# board.net
KiCad netlist of a schematic drawn in EAGLE
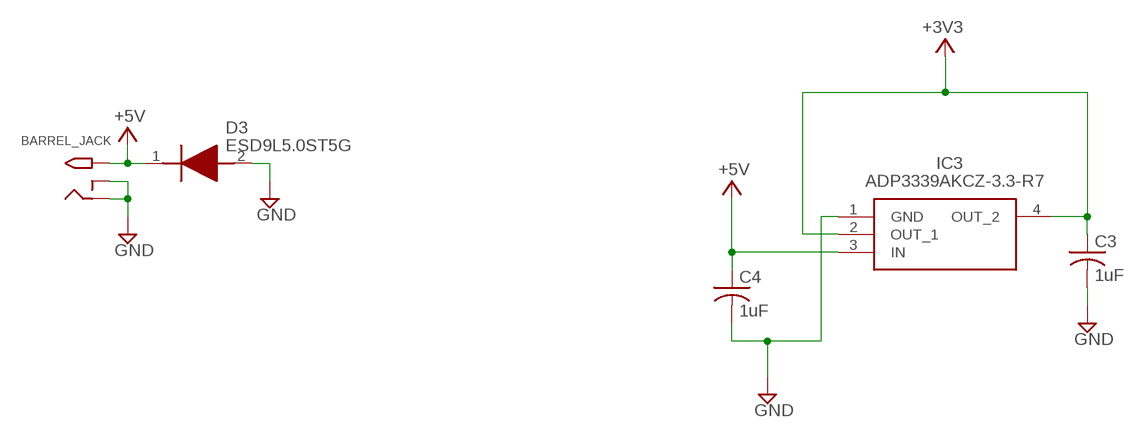
[diagram p0: schematic, sheet 1]
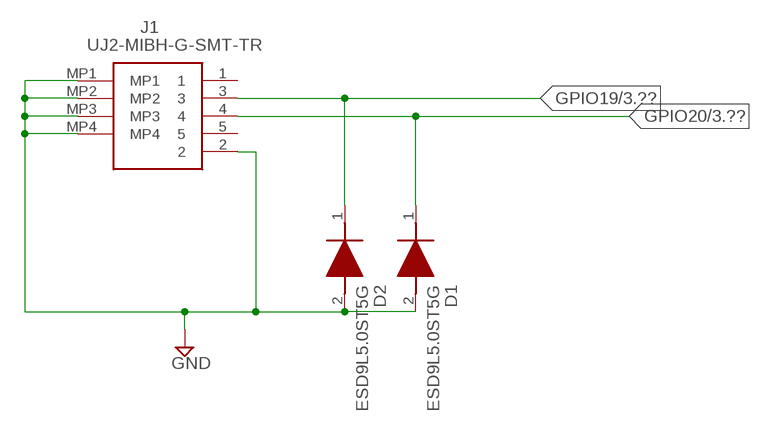
[diagram p1: schematic, sheet 2]
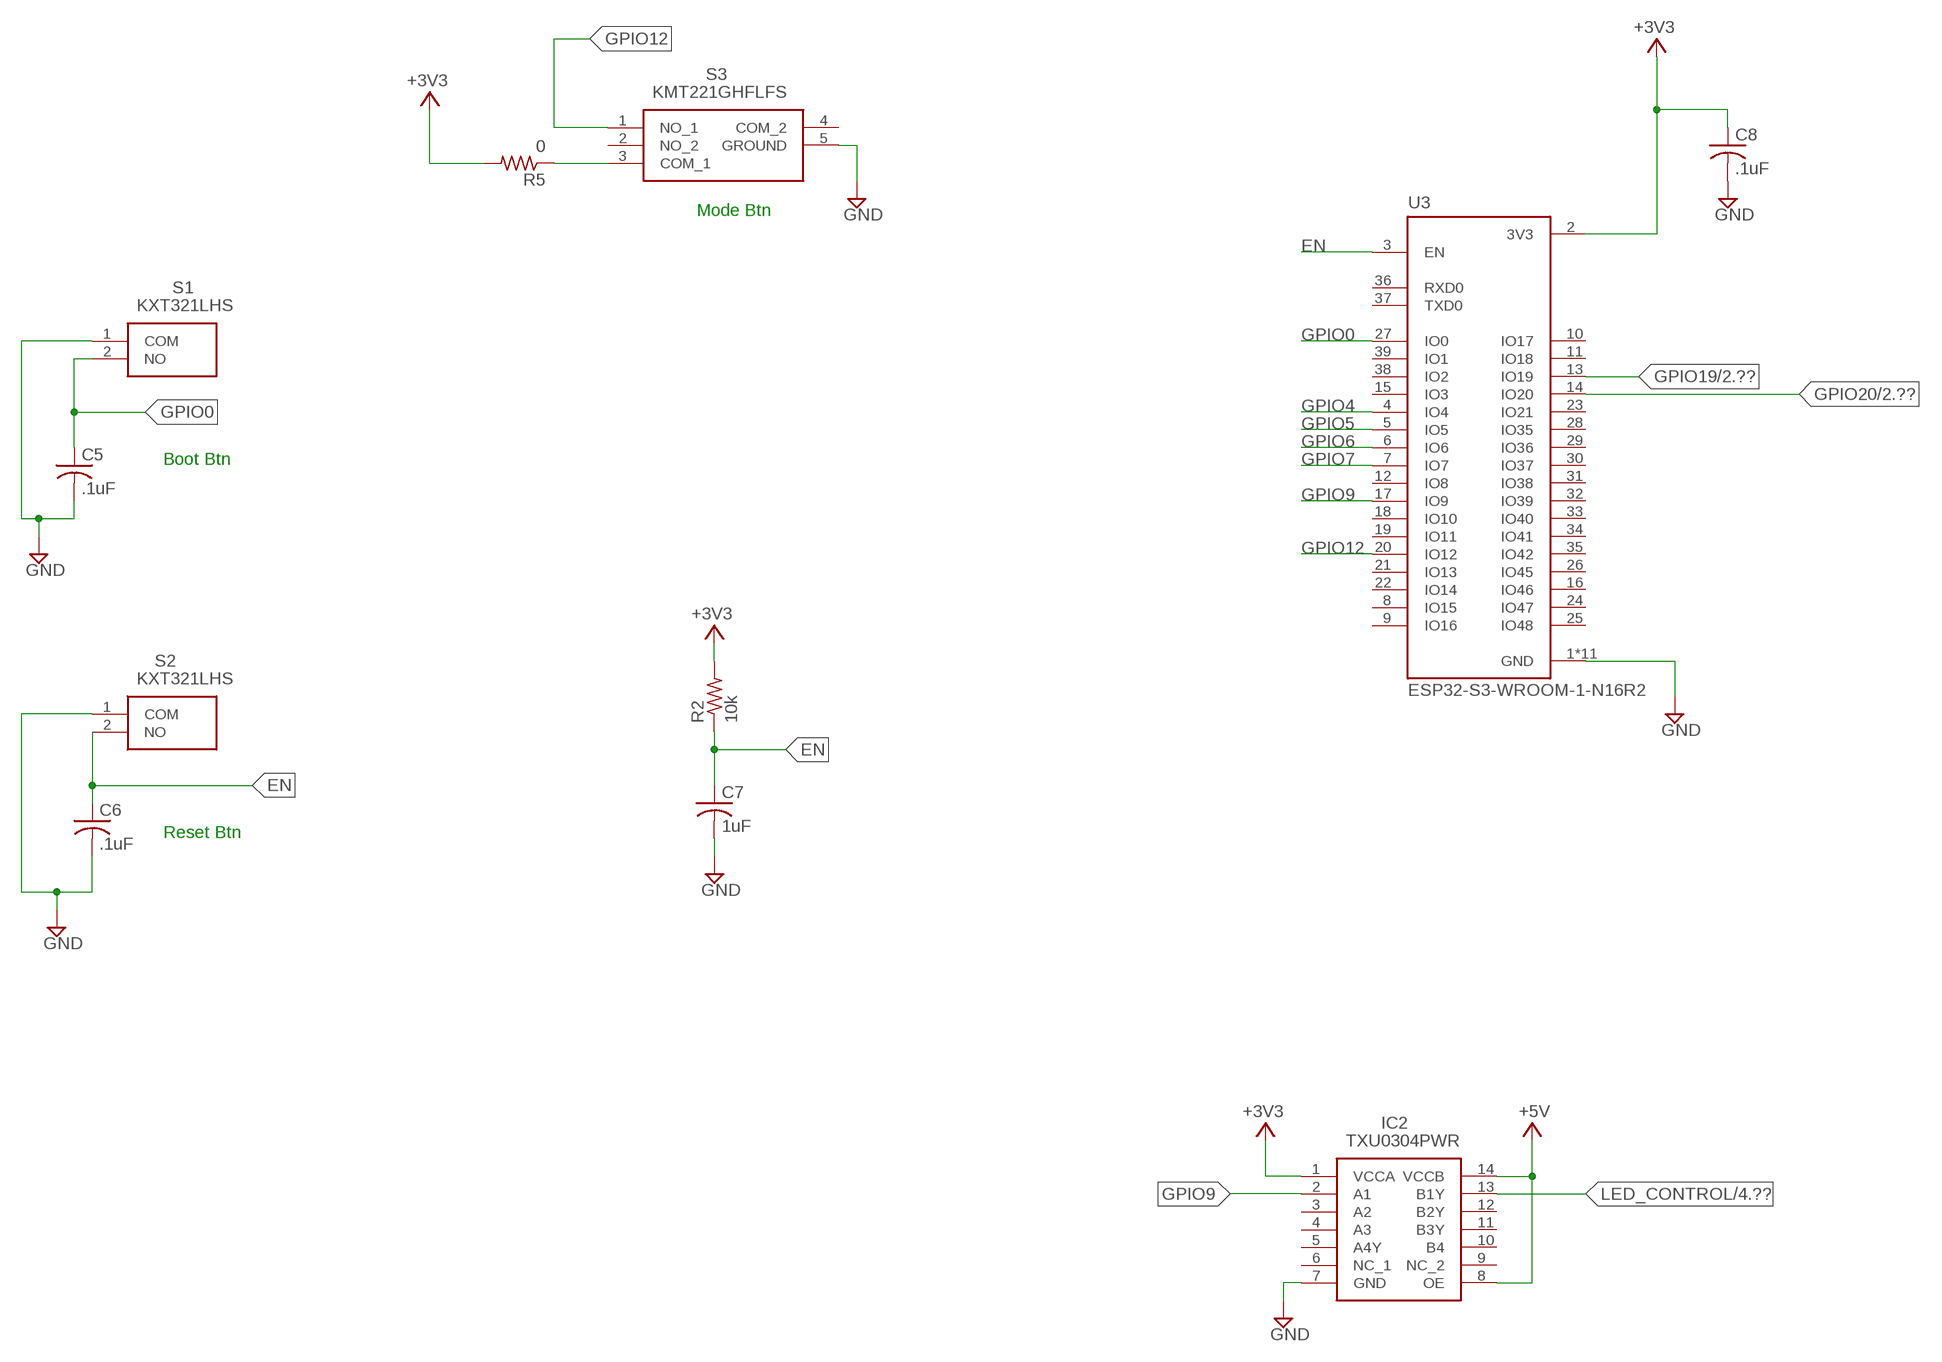
[diagram p2: schematic, sheet 3]
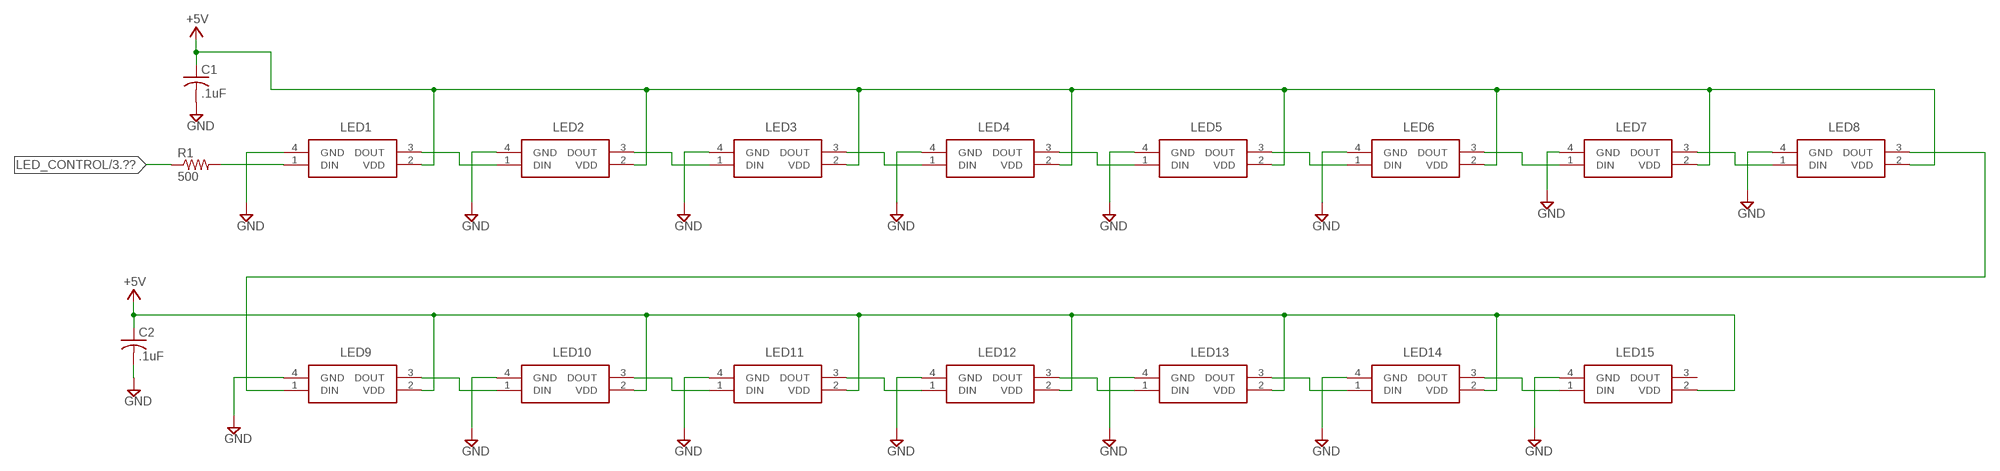
[diagram p3: schematic, sheet 4]
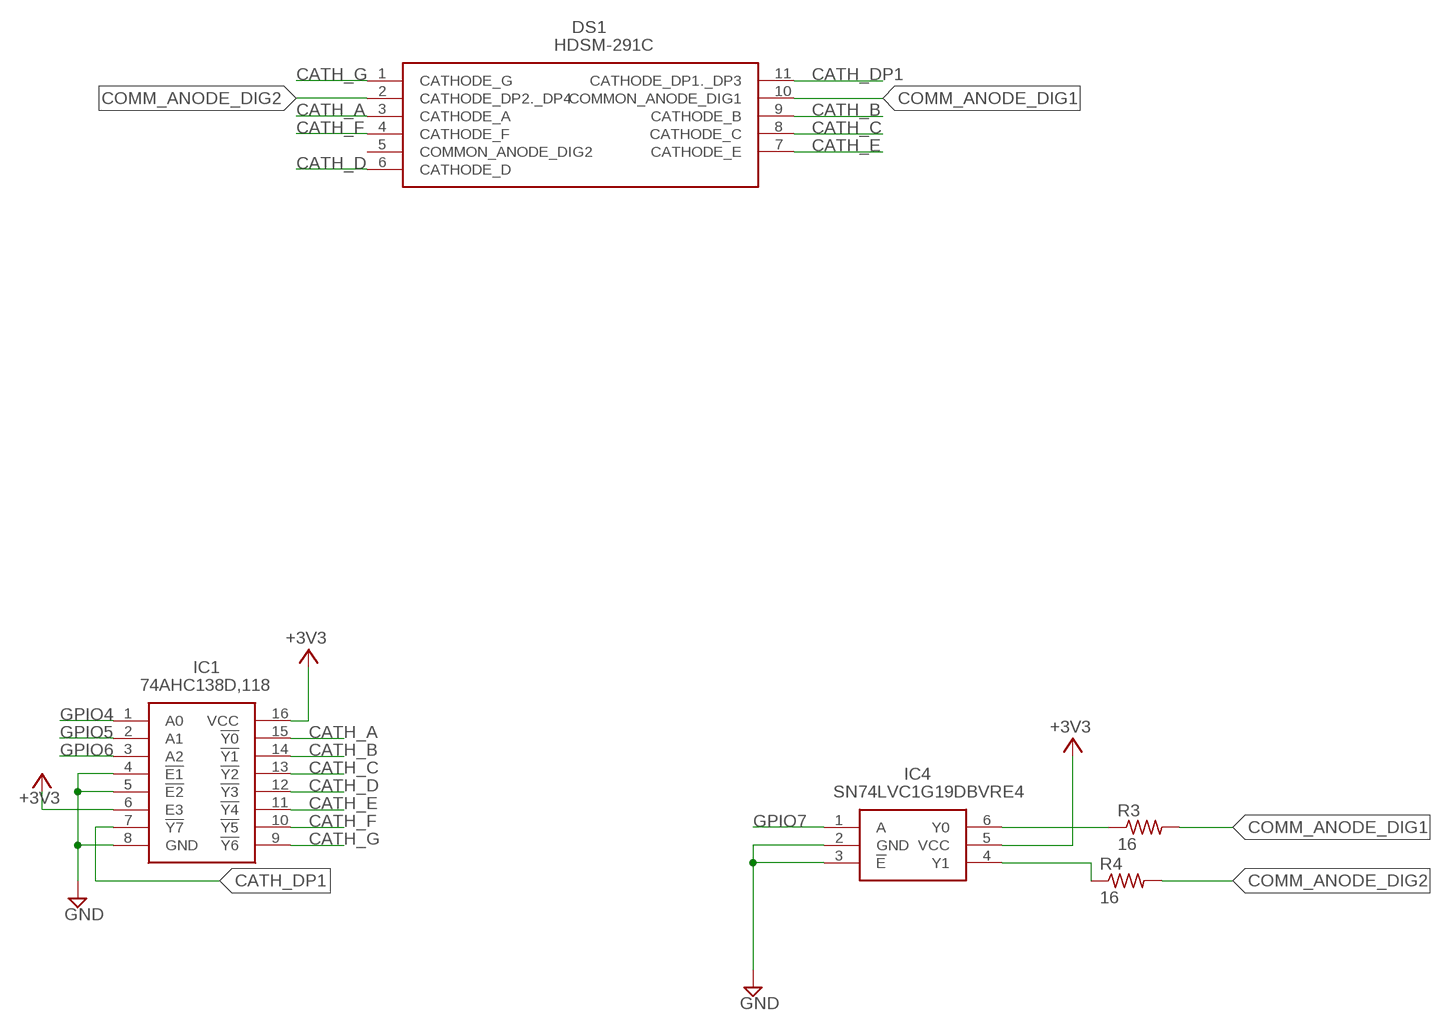
[diagram p4: schematic, sheet 5]

(export (version "E")
  (design (tool "Eeschema 10.0.6"))
  (components
    (comp (ref "BARREL_JACK")
      (value "2.1MMJACKTHM")
      (footprint "eagle-import:PJ-102A")
      (libsource (lib "eagle-import") (part "2.1MMJACKTHM"))
    )
    (comp (ref "C3")
      (value "1uF")
      (footprint "eagle-import:C0402")
      (libsource (lib "eagle-import") (part "C-USC0402"))
    )
    (comp (ref "C4")
      (value "1uF")
      (footprint "eagle-import:C0402")
      (libsource (lib "eagle-import") (part "C-USC0402"))
    )
    (comp (ref "D3")
      (value "ESD9L5.0ST5G")
      (footprint "eagle-import:SODFL1006X40N")
      (fields (field (name "MOUSER_PART_NUMBER") "863-ESD9L5.0ST5G"))
      (libsource (lib "eagle-import") (part "ESD9L5.0ST5G"))
    )
    (comp (ref "IC3")
      (value "ADP3339AKCZ-3.3-R7")
      (footprint "eagle-import:SOT230P700X180-4N")
      (fields (field (name "MOUSER_PART_NUMBER") "584-ADP3339AKCZ3.3R7"))
      (libsource (lib "eagle-import") (part "ADP3339AKCZ-3.3-R7"))
    )
    (comp (ref "DS1")
      (value "HDSM-291C")
      (footprint "eagle-import:HDSM291C")
      (fields (field (name "MOUSER_PART_NUMBER") "630-HDSM-291C"))
      (libsource (lib "eagle-import") (part "HDSM-291C"))
    )
    (comp (ref "IC1")
      (value "74AHC138D,118")
      (footprint "eagle-import:SOIC127P600X175-16N")
      (fields (field (name "MOUSER_PART_NUMBER") "771-74AHC138D-T"))
      (libsource (lib "eagle-import") (part "74AHC138D,118"))
    )
    (comp (ref "IC4")
      (value "SN74LVC1G19DBVRE4")
      (footprint "eagle-import:SOT95P280X145-6N")
      (fields (field (name "MOUSER_PART_NUMBER") "595-74LVC1G19DBVRE4"))
      (libsource (lib "eagle-import") (part "SN74LVC1G19DBVRE4"))
    )
    (comp (ref "R3")
      (value "16")
      (footprint "eagle-import:R0402")
      (libsource (lib "eagle-import") (part "R-US_R0402"))
    )
    (comp (ref "R4")
      (value "16")
      (footprint "eagle-import:R0402")
      (libsource (lib "eagle-import") (part "R-US_R0402"))
    )
    (comp (ref "C1")
      (value ".1uF")
      (footprint "eagle-import:C0402")
      (libsource (lib "eagle-import") (part "C-USC0402"))
    )
    (comp (ref "C2")
      (value ".1uF")
      (footprint "eagle-import:C0402")
      (libsource (lib "eagle-import") (part "C-USC0402"))
    )
    (comp (ref "LED1")
      (value "4492__SK6805-EC_15_")
      (footprint "eagle-import:4492SK6805EC15")
      (fields (field (name "MANUFACTURER_PART_NUMBER") "4492 (SK6805-EC 15)"))
      (libsource (lib "eagle-import") (part "4492__SK6805-EC_15_"))
    )
    (comp (ref "LED2")
      (value "4492__SK6805-EC_15_")
      (footprint "eagle-import:4492SK6805EC15")
      (fields (field (name "MANUFACTURER_PART_NUMBER") "4492 (SK6805-EC 15)"))
      (libsource (lib "eagle-import") (part "4492__SK6805-EC_15_"))
    )
    (comp (ref "LED3")
      (value "4492__SK6805-EC_15_")
      (footprint "eagle-import:4492SK6805EC15")
      (fields (field (name "MANUFACTURER_PART_NUMBER") "4492 (SK6805-EC 15)"))
      (libsource (lib "eagle-import") (part "4492__SK6805-EC_15_"))
    )
    (comp (ref "LED4")
      (value "4492__SK6805-EC_15_")
      (footprint "eagle-import:4492SK6805EC15")
      (fields (field (name "MANUFACTURER_PART_NUMBER") "4492 (SK6805-EC 15)"))
      (libsource (lib "eagle-import") (part "4492__SK6805-EC_15_"))
    )
    (comp (ref "LED5")
      (value "4492__SK6805-EC_15_")
      (footprint "eagle-import:4492SK6805EC15")
      (fields (field (name "MANUFACTURER_PART_NUMBER") "4492 (SK6805-EC 15)"))
      (libsource (lib "eagle-import") (part "4492__SK6805-EC_15_"))
    )
    (comp (ref "LED6")
      (value "4492__SK6805-EC_15_")
      (footprint "eagle-import:4492SK6805EC15")
      (fields (field (name "MANUFACTURER_PART_NUMBER") "4492 (SK6805-EC 15)"))
      (libsource (lib "eagle-import") (part "4492__SK6805-EC_15_"))
    )
    (comp (ref "LED7")
      (value "4492__SK6805-EC_15_")
      (footprint "eagle-import:4492SK6805EC15")
      (fields (field (name "MANUFACTURER_PART_NUMBER") "4492 (SK6805-EC 15)"))
      (libsource (lib "eagle-import") (part "4492__SK6805-EC_15_"))
    )
    (comp (ref "LED8")
      (value "4492__SK6805-EC_15_")
      (footprint "eagle-import:4492SK6805EC15")
      (fields (field (name "MANUFACTURER_PART_NUMBER") "4492 (SK6805-EC 15)"))
      (libsource (lib "eagle-import") (part "4492__SK6805-EC_15_"))
    )
    (comp (ref "LED9")
      (value "4492__SK6805-EC_15_")
      (footprint "eagle-import:4492SK6805EC15")
      (fields (field (name "MANUFACTURER_PART_NUMBER") "4492 (SK6805-EC 15)"))
      (libsource (lib "eagle-import") (part "4492__SK6805-EC_15_"))
    )
    (comp (ref "LED10")
      (value "4492__SK6805-EC_15_")
      (footprint "eagle-import:4492SK6805EC15")
      (fields (field (name "MANUFACTURER_PART_NUMBER") "4492 (SK6805-EC 15)"))
      (libsource (lib "eagle-import") (part "4492__SK6805-EC_15_"))
    )
    (comp (ref "LED11")
      (value "4492__SK6805-EC_15_")
      (footprint "eagle-import:4492SK6805EC15")
      (fields (field (name "MANUFACTURER_PART_NUMBER") "4492 (SK6805-EC 15)"))
      (libsource (lib "eagle-import") (part "4492__SK6805-EC_15_"))
    )
    (comp (ref "LED12")
      (value "4492__SK6805-EC_15_")
      (footprint "eagle-import:4492SK6805EC15")
      (fields (field (name "MANUFACTURER_PART_NUMBER") "4492 (SK6805-EC 15)"))
      (libsource (lib "eagle-import") (part "4492__SK6805-EC_15_"))
    )
    (comp (ref "LED13")
      (value "4492__SK6805-EC_15_")
      (footprint "eagle-import:4492SK6805EC15")
      (fields (field (name "MANUFACTURER_PART_NUMBER") "4492 (SK6805-EC 15)"))
      (libsource (lib "eagle-import") (part "4492__SK6805-EC_15_"))
    )
    (comp (ref "LED14")
      (value "4492__SK6805-EC_15_")
      (footprint "eagle-import:4492SK6805EC15")
      (fields (field (name "MANUFACTURER_PART_NUMBER") "4492 (SK6805-EC 15)"))
      (libsource (lib "eagle-import") (part "4492__SK6805-EC_15_"))
    )
    (comp (ref "LED15")
      (value "4492__SK6805-EC_15_")
      (footprint "eagle-import:4492SK6805EC15")
      (fields (field (name "MANUFACTURER_PART_NUMBER") "4492 (SK6805-EC 15)"))
      (libsource (lib "eagle-import") (part "4492__SK6805-EC_15_"))
    )
    (comp (ref "R1")
      (value "500")
      (footprint "eagle-import:R0402")
      (libsource (lib "eagle-import") (part "R-US_R0402"))
    )
    (comp (ref "C5")
      (value ".1uF")
      (footprint "eagle-import:C0402")
      (libsource (lib "eagle-import") (part "C-USC0402"))
    )
    (comp (ref "C6")
      (value ".1uF")
      (footprint "eagle-import:C0402")
      (libsource (lib "eagle-import") (part "C-USC0402"))
    )
    (comp (ref "C7")
      (value "1uF")
      (footprint "eagle-import:C0402")
      (libsource (lib "eagle-import") (part "C-USC0402"))
    )
    (comp (ref "C8")
      (value ".1uF")
      (footprint "eagle-import:C0402")
      (libsource (lib "eagle-import") (part "C-USC0402"))
    )
    (comp (ref "IC2")
      (value "TXU0304PWR")
      (footprint "eagle-import:SOP65P640X120-14N")
      (fields (field (name "MOUSER_PART_NUMBER") "595-TXU0304PWR"))
      (libsource (lib "eagle-import") (part "TXU0304PWR"))
    )
    (comp (ref "R2")
      (value "10k")
      (footprint "eagle-import:R0402")
      (libsource (lib "eagle-import") (part "R-US_R0402"))
    )
    (comp (ref "R5")
      (value "0")
      (footprint "eagle-import:R0402")
      (libsource (lib "eagle-import") (part "R-US_R0402"))
    )
    (comp (ref "S1")
      (value "KXT321LHS")
      (footprint "eagle-import:KXT321LHS")
      (fields (field (name "MOUSER_PART_NUMBER") "611-KXT321LHS"))
      (libsource (lib "eagle-import") (part "KXT321LHS"))
    )
    (comp (ref "S2")
      (value "KXT321LHS")
      (footprint "eagle-import:KXT321LHS")
      (fields (field (name "MOUSER_PART_NUMBER") "611-KXT321LHS"))
      (libsource (lib "eagle-import") (part "KXT321LHS"))
    )
    (comp (ref "S3")
      (value "KMT221GHFLFS")
      (footprint "eagle-import:KMT221GHFLFS")
      (fields (field (name "MOUSER_PART_NUMBER") "611-KMT221GHFLFS"))
      (libsource (lib "eagle-import") (part "KMT221GHFLFS"))
    )
    (comp (ref "U3")
      (value "ESP32-S3-WROOM-1-N16R2")
      (footprint "eagle-import:XCVR_ESP32-S3-WROOM-1-N16R2")
      (fields (field (name "MF") "Espressif Systems"))
      (libsource (lib "eagle-import") (part "ESP32-S3-WROOM-1-N16R2"))
    )
    (comp (ref "D1")
      (value "ESD9L5.0ST5G")
      (footprint "eagle-import:SODFL1006X40N")
      (fields (field (name "MOUSER_PART_NUMBER") "863-ESD9L5.0ST5G"))
      (libsource (lib "eagle-import") (part "ESD9L5.0ST5G"))
    )
    (comp (ref "D2")
      (value "ESD9L5.0ST5G")
      (footprint "eagle-import:SODFL1006X40N")
      (fields (field (name "MOUSER_PART_NUMBER") "863-ESD9L5.0ST5G"))
      (libsource (lib "eagle-import") (part "ESD9L5.0ST5G"))
    )
    (comp (ref "J1")
      (value "UJ2-MIBH-G-SMT-TR")
      (footprint "eagle-import:UJ2MIBHGSMTTR")
      (fields (field (name "MOUSER_PART_NUMBER") "490-UJ2-MIBH-G-SMTTR"))
      (libsource (lib "eagle-import") (part "UJ2-MIBH-G-SMT-TR"))
    )
  )
  (nets
    (net (code "1") (name "+3V3") (class "Default")
      (node (ref "C3") (pin "1") (pinfunction "1_1") (pintype "passive"))
      (node (ref "C8") (pin "1") (pinfunction "1_1") (pintype "passive"))
      (node (ref "IC1") (pin "16") (pinfunction "VCC_16") (pintype "bidirectional"))
      (node (ref "IC1") (pin "6") (pinfunction "E3_6") (pintype "bidirectional"))
      (node (ref "IC2") (pin "1") (pinfunction "VCCA_1") (pintype "bidirectional"))
      (node (ref "IC3") (pin "2") (pinfunction "OUT_1_2") (pintype "bidirectional"))
      (node (ref "IC3") (pin "4") (pinfunction "OUT_2_4") (pintype "bidirectional"))
      (node (ref "IC4") (pin "5") (pinfunction "VCC_5") (pintype "bidirectional"))
      (node (ref "R2") (pin "2") (pinfunction "2_2") (pintype "passive"))
      (node (ref "R5") (pin "2") (pinfunction "2_2") (pintype "passive"))
      (node (ref "U3") (pin "2") (pinfunction "3V3_2") (pintype "power_in"))
    )
    (net (code "2") (name "+5V") (class "Default")
      (node (ref "BARREL_JACK") (pin "TIP") (pinfunction "TIP_TIP") (pintype "bidirectional"))
      (node (ref "C1") (pin "1") (pinfunction "1_1") (pintype "passive"))
      (node (ref "C2") (pin "1") (pinfunction "1_1") (pintype "passive"))
      (node (ref "C4") (pin "1") (pinfunction "1_1") (pintype "passive"))
      (node (ref "D3") (pin "1") (pinfunction "K_1") (pintype "bidirectional"))
      (node (ref "IC2") (pin "14") (pinfunction "VCCB_14") (pintype "bidirectional"))
      (node (ref "IC2") (pin "8") (pinfunction "OE_8") (pintype "bidirectional"))
      (node (ref "IC3") (pin "3") (pinfunction "IN_3") (pintype "bidirectional"))
      (node (ref "LED1") (pin "2") (pinfunction "VDD_2") (pintype "bidirectional"))
      (node (ref "LED10") (pin "2") (pinfunction "VDD_2") (pintype "bidirectional"))
      (node (ref "LED11") (pin "2") (pinfunction "VDD_2") (pintype "bidirectional"))
      (node (ref "LED12") (pin "2") (pinfunction "VDD_2") (pintype "bidirectional"))
      (node (ref "LED13") (pin "2") (pinfunction "VDD_2") (pintype "bidirectional"))
      (node (ref "LED14") (pin "2") (pinfunction "VDD_2") (pintype "bidirectional"))
      (node (ref "LED15") (pin "2") (pinfunction "VDD_2") (pintype "bidirectional"))
      (node (ref "LED2") (pin "2") (pinfunction "VDD_2") (pintype "bidirectional"))
      (node (ref "LED3") (pin "2") (pinfunction "VDD_2") (pintype "bidirectional"))
      (node (ref "LED4") (pin "2") (pinfunction "VDD_2") (pintype "bidirectional"))
      (node (ref "LED5") (pin "2") (pinfunction "VDD_2") (pintype "bidirectional"))
      (node (ref "LED6") (pin "2") (pinfunction "VDD_2") (pintype "bidirectional"))
      (node (ref "LED7") (pin "2") (pinfunction "VDD_2") (pintype "bidirectional"))
      (node (ref "LED8") (pin "2") (pinfunction "VDD_2") (pintype "bidirectional"))
      (node (ref "LED9") (pin "2") (pinfunction "VDD_2") (pintype "bidirectional"))
    )
    (net (code "3") (name "CATH_A") (class "Default")
      (node (ref "DS1") (pin "3") (pinfunction "CATHODE_A_3") (pintype "bidirectional"))
      (node (ref "IC1") (pin "15") (pinfunction "~{Y0}_15") (pintype "bidirectional"))
    )
    (net (code "4") (name "CATH_B") (class "Default")
      (node (ref "DS1") (pin "9") (pinfunction "CATHODE_B_9") (pintype "bidirectional"))
      (node (ref "IC1") (pin "14") (pinfunction "~{Y1}_14") (pintype "bidirectional"))
    )
    (net (code "5") (name "CATH_C") (class "Default")
      (node (ref "DS1") (pin "8") (pinfunction "CATHODE_C_8") (pintype "bidirectional"))
      (node (ref "IC1") (pin "13") (pinfunction "~{Y2}_13") (pintype "bidirectional"))
    )
    (net (code "6") (name "CATH_D") (class "Default")
      (node (ref "DS1") (pin "6") (pinfunction "CATHODE_D_6") (pintype "bidirectional"))
      (node (ref "IC1") (pin "12") (pinfunction "~{Y3}_12") (pintype "bidirectional"))
    )
    (net (code "7") (name "CATH_DP1") (class "Default")
      (node (ref "DS1") (pin "11") (pinfunction "CATHODE_DP1._DP3_11") (pintype "bidirectional"))
      (node (ref "IC1") (pin "7") (pinfunction "~{Y7}_7") (pintype "bidirectional"))
    )
    (net (code "8") (name "CATH_E") (class "Default")
      (node (ref "DS1") (pin "7") (pinfunction "CATHODE_E_7") (pintype "bidirectional"))
      (node (ref "IC1") (pin "11") (pinfunction "~{Y4}_11") (pintype "bidirectional"))
    )
    (net (code "9") (name "CATH_F") (class "Default")
      (node (ref "DS1") (pin "4") (pinfunction "CATHODE_F_4") (pintype "bidirectional"))
      (node (ref "IC1") (pin "10") (pinfunction "~{Y5}_10") (pintype "bidirectional"))
    )
    (net (code "10") (name "CATH_G") (class "Default")
      (node (ref "DS1") (pin "1") (pinfunction "CATHODE_G_1") (pintype "bidirectional"))
      (node (ref "IC1") (pin "9") (pinfunction "~{Y6}_9") (pintype "bidirectional"))
    )
    (net (code "11") (name "COMM_ANODE_DIG1") (class "Default")
      (node (ref "DS1") (pin "10") (pinfunction "COMMON_ANODE_DIG1_10") (pintype "bidirectional"))
      (node (ref "R3") (pin "2") (pinfunction "2_2") (pintype "passive"))
    )
    (net (code "12") (name "COMM_ANODE_DIG2") (class "Default")
      (node (ref "DS1") (pin "2") (pinfunction "CATHODE_DP2._DP4_2") (pintype "bidirectional"))
      (node (ref "R4") (pin "2") (pinfunction "2_2") (pintype "passive"))
    )
    (net (code "13") (name "EN") (class "Default")
      (node (ref "C6") (pin "1") (pinfunction "1_1") (pintype "passive"))
      (node (ref "C7") (pin "1") (pinfunction "1_1") (pintype "passive"))
      (node (ref "R2") (pin "1") (pinfunction "1_1") (pintype "passive"))
      (node (ref "S2") (pin "2") (pinfunction "NO_2") (pintype "bidirectional"))
      (node (ref "U3") (pin "3") (pinfunction "EN_3") (pintype "input"))
    )
    (net (code "14") (name "GND") (class "Default")
      (node (ref "BARREL_JACK") (pin "RING") (pinfunction "RING_RING") (pintype "bidirectional"))
      (node (ref "BARREL_JACK") (pin "RING_SW") (pinfunction "RING_SW_RING_SW") (pintype "bidirectional"))
      (node (ref "C1") (pin "2") (pinfunction "2_2") (pintype "passive"))
      (node (ref "C2") (pin "2") (pinfunction "2_2") (pintype "passive"))
      (node (ref "C3") (pin "2") (pinfunction "2_2") (pintype "passive"))
      (node (ref "C4") (pin "2") (pinfunction "2_2") (pintype "passive"))
      (node (ref "C5") (pin "2") (pinfunction "2_2") (pintype "passive"))
      (node (ref "C6") (pin "2") (pinfunction "2_2") (pintype "passive"))
      (node (ref "C7") (pin "2") (pinfunction "2_2") (pintype "passive"))
      (node (ref "C8") (pin "2") (pinfunction "2_2") (pintype "passive"))
      (node (ref "D1") (pin "2") (pinfunction "A_2") (pintype "bidirectional"))
      (node (ref "D2") (pin "2") (pinfunction "A_2") (pintype "bidirectional"))
      (node (ref "D3") (pin "2") (pinfunction "A_2") (pintype "bidirectional"))
      (node (ref "IC1") (pin "4") (pinfunction "~{E1}_4") (pintype "bidirectional"))
      (node (ref "IC1") (pin "5") (pinfunction "~{E2}_5") (pintype "bidirectional"))
      (node (ref "IC1") (pin "8") (pinfunction "GND_8") (pintype "bidirectional"))
      (node (ref "IC2") (pin "7") (pinfunction "GND_7") (pintype "bidirectional"))
      (node (ref "IC3") (pin "1") (pinfunction "GND_1") (pintype "bidirectional"))
      (node (ref "IC4") (pin "2") (pinfunction "GND_2") (pintype "bidirectional"))
      (node (ref "IC4") (pin "3") (pinfunction "~{E}_3") (pintype "bidirectional"))
      (node (ref "J1") (pin "2") (pinfunction "2_2") (pintype "bidirectional"))
      (node (ref "J1") (pin "MP1") (pinfunction "MP1_MP1") (pintype "bidirectional"))
      (node (ref "J1") (pin "MP2") (pinfunction "MP2_MP2") (pintype "bidirectional"))
      (node (ref "J1") (pin "MP3") (pinfunction "MP3_MP3") (pintype "bidirectional"))
      (node (ref "J1") (pin "MP4") (pinfunction "MP4_MP4") (pintype "bidirectional"))
      (node (ref "LED1") (pin "4") (pinfunction "GND_4") (pintype "bidirectional"))
      (node (ref "LED10") (pin "4") (pinfunction "GND_4") (pintype "bidirectional"))
      (node (ref "LED11") (pin "4") (pinfunction "GND_4") (pintype "bidirectional"))
      (node (ref "LED12") (pin "4") (pinfunction "GND_4") (pintype "bidirectional"))
      (node (ref "LED13") (pin "4") (pinfunction "GND_4") (pintype "bidirectional"))
      (node (ref "LED14") (pin "4") (pinfunction "GND_4") (pintype "bidirectional"))
      (node (ref "LED15") (pin "4") (pinfunction "GND_4") (pintype "bidirectional"))
      (node (ref "LED2") (pin "4") (pinfunction "GND_4") (pintype "bidirectional"))
      (node (ref "LED3") (pin "4") (pinfunction "GND_4") (pintype "bidirectional"))
      (node (ref "LED4") (pin "4") (pinfunction "GND_4") (pintype "bidirectional"))
      (node (ref "LED5") (pin "4") (pinfunction "GND_4") (pintype "bidirectional"))
      (node (ref "LED6") (pin "4") (pinfunction "GND_4") (pintype "bidirectional"))
      (node (ref "LED7") (pin "4") (pinfunction "GND_4") (pintype "bidirectional"))
      (node (ref "LED8") (pin "4") (pinfunction "GND_4") (pintype "bidirectional"))
      (node (ref "LED9") (pin "4") (pinfunction "GND_4") (pintype "bidirectional"))
      (node (ref "S1") (pin "1") (pinfunction "COM_1") (pintype "bidirectional"))
      (node (ref "S2") (pin "1") (pinfunction "COM_1") (pintype "bidirectional"))
      (node (ref "S3") (pin "5") (pinfunction "GROUND_5") (pintype "bidirectional"))
      (node (ref "U3") (pin "1") (pinfunction "GND_1") (pintype "power_in"))
      (node (ref "U3") (pin "40") (pinfunction "GND_40") (pintype "power_in"))
      (node (ref "U3") (pin "41_1") (pinfunction "GND_41_1") (pintype "power_in"))
      (node (ref "U3") (pin "41_2") (pinfunction "GND_41_2") (pintype "power_in"))
      (node (ref "U3") (pin "41_3") (pinfunction "GND_41_3") (pintype "power_in"))
      (node (ref "U3") (pin "41_4") (pinfunction "GND_41_4") (pintype "power_in"))
      (node (ref "U3") (pin "41_5") (pinfunction "GND_41_5") (pintype "power_in"))
      (node (ref "U3") (pin "41_6") (pinfunction "GND_41_6") (pintype "power_in"))
      (node (ref "U3") (pin "41_7") (pinfunction "GND_41_7") (pintype "power_in"))
      (node (ref "U3") (pin "41_8") (pinfunction "GND_41_8") (pintype "power_in"))
      (node (ref "U3") (pin "41_9") (pinfunction "GND_41_9") (pintype "power_in"))
    )
    (net (code "15") (name "GPIO0") (class "Default")
      (node (ref "C5") (pin "1") (pinfunction "1_1") (pintype "passive"))
      (node (ref "S1") (pin "2") (pinfunction "NO_2") (pintype "bidirectional"))
      (node (ref "U3") (pin "27") (pinfunction "IO0_27") (pintype "bidirectional"))
    )
    (net (code "16") (name "GPIO4") (class "Default")
      (node (ref "IC1") (pin "1") (pinfunction "A0_1") (pintype "bidirectional"))
      (node (ref "U3") (pin "4") (pinfunction "IO4_4") (pintype "bidirectional"))
    )
    (net (code "17") (name "GPIO5") (class "Default")
      (node (ref "IC1") (pin "2") (pinfunction "A1_2") (pintype "bidirectional"))
      (node (ref "U3") (pin "5") (pinfunction "IO5_5") (pintype "bidirectional"))
    )
    (net (code "18") (name "GPIO6") (class "Default")
      (node (ref "IC1") (pin "3") (pinfunction "A2_3") (pintype "bidirectional"))
      (node (ref "U3") (pin "6") (pinfunction "IO6_6") (pintype "bidirectional"))
    )
    (net (code "19") (name "GPIO7") (class "Default")
      (node (ref "IC4") (pin "1") (pinfunction "A_1") (pintype "bidirectional"))
      (node (ref "U3") (pin "7") (pinfunction "IO7_7") (pintype "bidirectional"))
    )
    (net (code "20") (name "GPIO9") (class "Default")
      (node (ref "IC2") (pin "2") (pinfunction "A1_2") (pintype "bidirectional"))
      (node (ref "U3") (pin "17") (pinfunction "IO9_17") (pintype "bidirectional"))
    )
    (net (code "21") (name "GPIO12") (class "Default")
      (node (ref "S3") (pin "1") (pinfunction "NO_1_1") (pintype "bidirectional"))
      (node (ref "U3") (pin "20") (pinfunction "IO12_20") (pintype "bidirectional"))
    )
    (net (code "22") (name "GPIO19") (class "Default")
      (node (ref "D2") (pin "1") (pinfunction "K_1") (pintype "bidirectional"))
      (node (ref "J1") (pin "3") (pinfunction "3_3") (pintype "bidirectional"))
      (node (ref "U3") (pin "13") (pinfunction "IO19_13") (pintype "bidirectional"))
    )
    (net (code "23") (name "GPIO20") (class "Default")
      (node (ref "D1") (pin "1") (pinfunction "K_1") (pintype "bidirectional"))
      (node (ref "J1") (pin "4") (pinfunction "4_4") (pintype "bidirectional"))
      (node (ref "U3") (pin "14") (pinfunction "IO20_14") (pintype "bidirectional"))
    )
    (net (code "24") (name "LED_CONTROL") (class "Default")
      (node (ref "IC2") (pin "13") (pinfunction "B1Y_13") (pintype "bidirectional"))
      (node (ref "R1") (pin "1") (pinfunction "1_1") (pintype "passive"))
    )
    (net (code "25") (name "Net-(IC4-Y0)") (class "Default")
      (node (ref "IC4") (pin "6") (pinfunction "Y0_6") (pintype "bidirectional"))
      (node (ref "R3") (pin "1") (pinfunction "1_1") (pintype "passive"))
    )
    (net (code "26") (name "Net-(IC4-Y1)") (class "Default")
      (node (ref "IC4") (pin "4") (pinfunction "Y1_4") (pintype "bidirectional"))
      (node (ref "R4") (pin "1") (pinfunction "1_1") (pintype "passive"))
    )
    (net (code "27") (name "Net-(LED1-DIN)") (class "Default")
      (node (ref "LED1") (pin "1") (pinfunction "DIN_1") (pintype "bidirectional"))
      (node (ref "R1") (pin "2") (pinfunction "2_2") (pintype "passive"))
    )
    (net (code "28") (name "Net-(LED1-DOUT)") (class "Default")
      (node (ref "LED1") (pin "3") (pinfunction "DOUT_3") (pintype "bidirectional"))
      (node (ref "LED2") (pin "1") (pinfunction "DIN_1") (pintype "bidirectional"))
    )
    (net (code "29") (name "Net-(LED2-DOUT)") (class "Default")
      (node (ref "LED2") (pin "3") (pinfunction "DOUT_3") (pintype "bidirectional"))
      (node (ref "LED3") (pin "1") (pinfunction "DIN_1") (pintype "bidirectional"))
    )
    (net (code "30") (name "Net-(LED3-DOUT)") (class "Default")
      (node (ref "LED3") (pin "3") (pinfunction "DOUT_3") (pintype "bidirectional"))
      (node (ref "LED4") (pin "1") (pinfunction "DIN_1") (pintype "bidirectional"))
    )
    (net (code "31") (name "Net-(LED4-DOUT)") (class "Default")
      (node (ref "LED4") (pin "3") (pinfunction "DOUT_3") (pintype "bidirectional"))
      (node (ref "LED5") (pin "1") (pinfunction "DIN_1") (pintype "bidirectional"))
    )
    (net (code "32") (name "Net-(LED5-DOUT)") (class "Default")
      (node (ref "LED5") (pin "3") (pinfunction "DOUT_3") (pintype "bidirectional"))
      (node (ref "LED6") (pin "1") (pinfunction "DIN_1") (pintype "bidirectional"))
    )
    (net (code "33") (name "Net-(LED6-DOUT)") (class "Default")
      (node (ref "LED6") (pin "3") (pinfunction "DOUT_3") (pintype "bidirectional"))
      (node (ref "LED7") (pin "1") (pinfunction "DIN_1") (pintype "bidirectional"))
    )
    (net (code "34") (name "Net-(LED7-DOUT)") (class "Default")
      (node (ref "LED7") (pin "3") (pinfunction "DOUT_3") (pintype "bidirectional"))
      (node (ref "LED8") (pin "1") (pinfunction "DIN_1") (pintype "bidirectional"))
    )
    (net (code "35") (name "Net-(LED8-DOUT)") (class "Default")
      (node (ref "LED8") (pin "3") (pinfunction "DOUT_3") (pintype "bidirectional"))
      (node (ref "LED9") (pin "1") (pinfunction "DIN_1") (pintype "bidirectional"))
    )
    (net (code "36") (name "Net-(LED10-DIN)") (class "Default")
      (node (ref "LED10") (pin "1") (pinfunction "DIN_1") (pintype "bidirectional"))
      (node (ref "LED9") (pin "3") (pinfunction "DOUT_3") (pintype "bidirectional"))
    )
    (net (code "37") (name "Net-(LED10-DOUT)") (class "Default")
      (node (ref "LED10") (pin "3") (pinfunction "DOUT_3") (pintype "bidirectional"))
      (node (ref "LED11") (pin "1") (pinfunction "DIN_1") (pintype "bidirectional"))
    )
    (net (code "38") (name "Net-(LED11-DOUT)") (class "Default")
      (node (ref "LED11") (pin "3") (pinfunction "DOUT_3") (pintype "bidirectional"))
      (node (ref "LED12") (pin "1") (pinfunction "DIN_1") (pintype "bidirectional"))
    )
    (net (code "39") (name "Net-(LED12-DOUT)") (class "Default")
      (node (ref "LED12") (pin "3") (pinfunction "DOUT_3") (pintype "bidirectional"))
      (node (ref "LED13") (pin "1") (pinfunction "DIN_1") (pintype "bidirectional"))
    )
    (net (code "40") (name "Net-(LED13-DOUT)") (class "Default")
      (node (ref "LED13") (pin "3") (pinfunction "DOUT_3") (pintype "bidirectional"))
      (node (ref "LED14") (pin "1") (pinfunction "DIN_1") (pintype "bidirectional"))
    )
    (net (code "41") (name "Net-(LED14-DOUT)") (class "Default")
      (node (ref "LED14") (pin "3") (pinfunction "DOUT_3") (pintype "bidirectional"))
      (node (ref "LED15") (pin "1") (pinfunction "DIN_1") (pintype "bidirectional"))
    )
    (net (code "42") (name "Net-(S3-COM_1)") (class "Default")
      (node (ref "R5") (pin "1") (pinfunction "1_1") (pintype "passive"))
      (node (ref "S3") (pin "3") (pinfunction "COM_1_3") (pintype "bidirectional"))
    )
    (net (code "43") (name "unconnected-(DS1-COMMON_ANODE_DIG2-Pad5)") (class "Default")
      (node (ref "DS1") (pin "5") (pinfunction "COMMON_ANODE_DIG2_5") (pintype "bidirectional"))
    )
    (net (code "44") (name "unconnected-(IC2-A2-Pad3)") (class "Default")
      (node (ref "IC2") (pin "3") (pinfunction "A2_3") (pintype "bidirectional"))
    )
    (net (code "45") (name "unconnected-(IC2-A3-Pad4)") (class "Default")
      (node (ref "IC2") (pin "4") (pinfunction "A3_4") (pintype "bidirectional"))
    )
    (net (code "46") (name "unconnected-(IC2-A4Y-Pad5)") (class "Default")
      (node (ref "IC2") (pin "5") (pinfunction "A4Y_5") (pintype "bidirectional"))
    )
    (net (code "47") (name "unconnected-(IC2-B2Y-Pad12)") (class "Default")
      (node (ref "IC2") (pin "12") (pinfunction "B2Y_12") (pintype "bidirectional"))
    )
    (net (code "48") (name "unconnected-(IC2-B3Y-Pad11)") (class "Default")
      (node (ref "IC2") (pin "11") (pinfunction "B3Y_11") (pintype "bidirectional"))
    )
    (net (code "49") (name "unconnected-(IC2-B4-Pad10)") (class "Default")
      (node (ref "IC2") (pin "10") (pinfunction "B4_10") (pintype "bidirectional"))
    )
    (net (code "50") (name "unconnected-(IC2-NC_1-Pad6)") (class "Default")
      (node (ref "IC2") (pin "6") (pinfunction "NC_1_6") (pintype "bidirectional"))
    )
    (net (code "51") (name "unconnected-(IC2-NC_2-Pad9)") (class "Default")
      (node (ref "IC2") (pin "9") (pinfunction "NC_2_9") (pintype "bidirectional"))
    )
    (net (code "52") (name "unconnected-(J1-Pad1)") (class "Default")
      (node (ref "J1") (pin "1") (pinfunction "1_1") (pintype "bidirectional"))
    )
    (net (code "53") (name "unconnected-(J1-Pad5)") (class "Default")
      (node (ref "J1") (pin "5") (pinfunction "5_5") (pintype "bidirectional"))
    )
    (net (code "54") (name "unconnected-(LED15-DOUT-Pad3)") (class "Default")
      (node (ref "LED15") (pin "3") (pinfunction "DOUT_3") (pintype "bidirectional"))
    )
    (net (code "55") (name "unconnected-(S3-COM_2-Pad4)") (class "Default")
      (node (ref "S3") (pin "4") (pinfunction "COM_2_4") (pintype "bidirectional"))
    )
    (net (code "56") (name "unconnected-(S3-NO_2-Pad2)") (class "Default")
      (node (ref "S3") (pin "2") (pinfunction "NO_2_2") (pintype "bidirectional"))
    )
    (net (code "57") (name "unconnected-(U3-IO1-Pad39)") (class "Default")
      (node (ref "U3") (pin "39") (pinfunction "IO1_39") (pintype "bidirectional"))
    )
    (net (code "58") (name "unconnected-(U3-IO2-Pad38)") (class "Default")
      (node (ref "U3") (pin "38") (pinfunction "IO2_38") (pintype "bidirectional"))
    )
    (net (code "59") (name "unconnected-(U3-IO3-Pad15)") (class "Default")
      (node (ref "U3") (pin "15") (pinfunction "IO3_15") (pintype "bidirectional"))
    )
    (net (code "60") (name "unconnected-(U3-IO8-Pad12)") (class "Default")
      (node (ref "U3") (pin "12") (pinfunction "IO8_12") (pintype "bidirectional"))
    )
    (net (code "61") (name "unconnected-(U3-IO10-Pad18)") (class "Default")
      (node (ref "U3") (pin "18") (pinfunction "IO10_18") (pintype "bidirectional"))
    )
    (net (code "62") (name "unconnected-(U3-IO11-Pad19)") (class "Default")
      (node (ref "U3") (pin "19") (pinfunction "IO11_19") (pintype "bidirectional"))
    )
    (net (code "63") (name "unconnected-(U3-IO13-Pad21)") (class "Default")
      (node (ref "U3") (pin "21") (pinfunction "IO13_21") (pintype "bidirectional"))
    )
    (net (code "64") (name "unconnected-(U3-IO14-Pad22)") (class "Default")
      (node (ref "U3") (pin "22") (pinfunction "IO14_22") (pintype "bidirectional"))
    )
    (net (code "65") (name "unconnected-(U3-IO15-Pad8)") (class "Default")
      (node (ref "U3") (pin "8") (pinfunction "IO15_8") (pintype "bidirectional"))
    )
    (net (code "66") (name "unconnected-(U3-IO16-Pad9)") (class "Default")
      (node (ref "U3") (pin "9") (pinfunction "IO16_9") (pintype "bidirectional"))
    )
    (net (code "67") (name "unconnected-(U3-IO17-Pad10)") (class "Default")
      (node (ref "U3") (pin "10") (pinfunction "IO17_10") (pintype "bidirectional"))
    )
    (net (code "68") (name "unconnected-(U3-IO18-Pad11)") (class "Default")
      (node (ref "U3") (pin "11") (pinfunction "IO18_11") (pintype "bidirectional"))
    )
    (net (code "69") (name "unconnected-(U3-IO21-Pad23)") (class "Default")
      (node (ref "U3") (pin "23") (pinfunction "IO21_23") (pintype "bidirectional"))
    )
    (net (code "70") (name "unconnected-(U3-IO35-Pad28)") (class "Default")
      (node (ref "U3") (pin "28") (pinfunction "IO35_28") (pintype "bidirectional"))
    )
    (net (code "71") (name "unconnected-(U3-IO36-Pad29)") (class "Default")
      (node (ref "U3") (pin "29") (pinfunction "IO36_29") (pintype "bidirectional"))
    )
    (net (code "72") (name "unconnected-(U3-IO37-Pad30)") (class "Default")
      (node (ref "U3") (pin "30") (pinfunction "IO37_30") (pintype "bidirectional"))
    )
    (net (code "73") (name "unconnected-(U3-IO38-Pad31)") (class "Default")
      (node (ref "U3") (pin "31") (pinfunction "IO38_31") (pintype "bidirectional"))
    )
    (net (code "74") (name "unconnected-(U3-IO39-Pad32)") (class "Default")
      (node (ref "U3") (pin "32") (pinfunction "IO39_32") (pintype "bidirectional"))
    )
    (net (code "75") (name "unconnected-(U3-IO40-Pad33)") (class "Default")
      (node (ref "U3") (pin "33") (pinfunction "IO40_33") (pintype "bidirectional"))
    )
    (net (code "76") (name "unconnected-(U3-IO41-Pad34)") (class "Default")
      (node (ref "U3") (pin "34") (pinfunction "IO41_34") (pintype "bidirectional"))
    )
    (net (code "77") (name "unconnected-(U3-IO42-Pad35)") (class "Default")
      (node (ref "U3") (pin "35") (pinfunction "IO42_35") (pintype "bidirectional"))
    )
    (net (code "78") (name "unconnected-(U3-IO45-Pad26)") (class "Default")
      (node (ref "U3") (pin "26") (pinfunction "IO45_26") (pintype "bidirectional"))
    )
    (net (code "79") (name "unconnected-(U3-IO46-Pad16)") (class "Default")
      (node (ref "U3") (pin "16") (pinfunction "IO46_16") (pintype "bidirectional"))
    )
    (net (code "80") (name "unconnected-(U3-IO47-Pad24)") (class "Default")
      (node (ref "U3") (pin "24") (pinfunction "IO47_24") (pintype "bidirectional"))
    )
    (net (code "81") (name "unconnected-(U3-IO48-Pad25)") (class "Default")
      (node (ref "U3") (pin "25") (pinfunction "IO48_25") (pintype "bidirectional"))
    )
    (net (code "82") (name "unconnected-(U3-RXD0-Pad36)") (class "Default")
      (node (ref "U3") (pin "36") (pinfunction "RXD0_36") (pintype "bidirectional"))
    )
    (net (code "83") (name "unconnected-(U3-TXD0-Pad37)") (class "Default")
      (node (ref "U3") (pin "37") (pinfunction "TXD0_37") (pintype "bidirectional"))
    )
  )
)
